# ESP32-Cam-Pico-V2.net
KiCad netlist of a schematic drawn in EAGLE
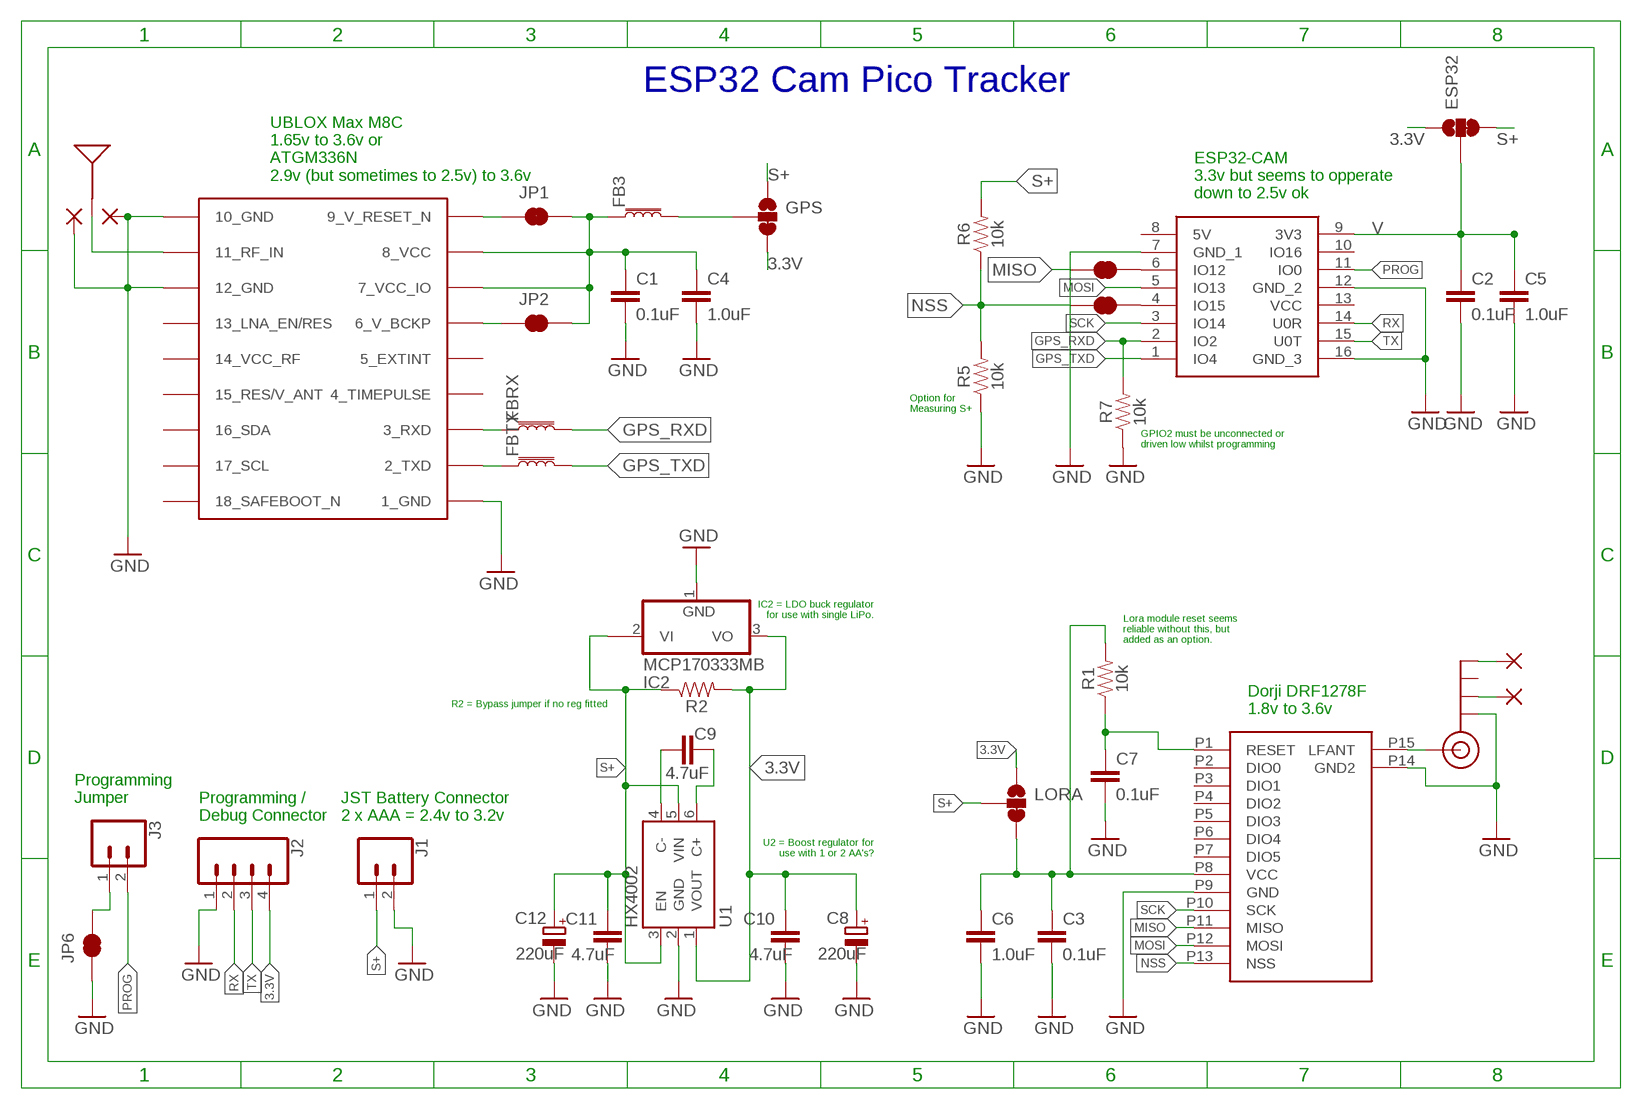
[diagram p0: schematic, sheet 1]

(export (version "E")
  (design (tool "Eeschema 10.0.6"))
  (components
    (comp (ref "C1")
      (value "0.1uF")
      (footprint "eagle-import:0402")
      (libsource (lib "eagle-import") (part "0.1UF-0402-6.3V-10%-X7R"))
    )
    (comp (ref "C2")
      (value "0.1uF")
      (footprint "eagle-import:0402")
      (libsource (lib "eagle-import") (part "0.1UF-0402-6.3V-10%-X7R"))
    )
    (comp (ref "C3")
      (value "0.1uF")
      (footprint "eagle-import:0402")
      (libsource (lib "eagle-import") (part "0.1UF-0402-6.3V-10%-X7R"))
    )
    (comp (ref "C4")
      (value "1.0uF")
      (footprint "eagle-import:0402")
      (libsource (lib "eagle-import") (part "1.0UF-0402-16V-10%"))
    )
    (comp (ref "C5")
      (value "1.0uF")
      (footprint "eagle-import:0402")
      (libsource (lib "eagle-import") (part "1.0UF-0402-16V-10%"))
    )
    (comp (ref "C6")
      (value "1.0uF")
      (footprint "eagle-import:0402")
      (libsource (lib "eagle-import") (part "1.0UF-0402-16V-10%"))
    )
    (comp (ref "C7")
      (value "0.1uF")
      (footprint "eagle-import:0402")
      (libsource (lib "eagle-import") (part "0.1UF-0402-6.3V-10%-X7R"))
    )
    (comp (ref "C8")
      (value "220uF")
      (footprint "eagle-import:SMC_C")
      (libsource (lib "eagle-import") (part "CPOL-EUSMCC"))
    )
    (comp (ref "C9")
      (value "4.7uF")
      (footprint "eagle-import:0402")
      (libsource (lib "eagle-import") (part "1.0UF-0402-16V-10%"))
    )
    (comp (ref "C10")
      (value "4.7uF")
      (footprint "eagle-import:0402")
      (libsource (lib "eagle-import") (part "1.0UF-0402-16V-10%"))
    )
    (comp (ref "C11")
      (value "4.7uF")
      (footprint "eagle-import:0402")
      (libsource (lib "eagle-import") (part "1.0UF-0402-16V-10%"))
    )
    (comp (ref "C12")
      (value "220uF")
      (footprint "eagle-import:SMC_C")
      (libsource (lib "eagle-import") (part "CPOL-EUSMCC"))
    )
    (comp (ref "ESP32")
      (value "JUMPER-SMT_3_1-NC_TRACE_SILK")
      (footprint "eagle-import:SMT-JUMPER_3_1-NC_TRACE_SILK")
      (libsource (lib "eagle-import") (part "JUMPER-SMT_3_1-NC_TRACE_SILK"))
    )
    (comp (ref "FB3")
      (value "FERRITE_BEAD-120_OHM-0402")
      (footprint "eagle-import:0402")
      (fields (field (name "MFG_PART") "BLM15HB121SN1D"))
      (libsource (lib "eagle-import") (part "FERRITE_BEAD-120_OHM-0402"))
    )
    (comp (ref "FBRX")
      (value "FERRITE_BEAD-120_OHM-0402")
      (footprint "eagle-import:0402")
      (fields (field (name "MFG_PART") "BLM15HB121SN1D"))
      (libsource (lib "eagle-import") (part "FERRITE_BEAD-120_OHM-0402"))
    )
    (comp (ref "FBTX")
      (value "FERRITE_BEAD-120_OHM-0402")
      (footprint "eagle-import:0402")
      (fields (field (name "MFG_PART") "BLM15HB121SN1D"))
      (libsource (lib "eagle-import") (part "FERRITE_BEAD-120_OHM-0402"))
    )
    (comp (ref "GPS")
      (value "JUMPER-SMT_3_1-NC_TRACE_SILK")
      (footprint "eagle-import:SMT-JUMPER_3_1-NC_TRACE_SILK")
      (libsource (lib "eagle-import") (part "JUMPER-SMT_3_1-NC_TRACE_SILK"))
    )
    (comp (ref "IC1")
      (value "ESP32-CAM")
      (footprint "eagle-import:ESP32CAM")
      (libsource (lib "eagle-import") (part "ESP32-CAM"))
    )
    (comp (ref "IC2")
      (value "MCP170333MB")
      (footprint "eagle-import:SOT89")
      (libsource (lib "eagle-import") (part "MCP1703MB33"))
    )
    (comp (ref "J$1")
      (value "SMA_EDGE")
      (footprint "eagle-import:SMA-EDGE")
      (libsource (lib "eagle-import") (part "SMA_EDGE"))
    )
    (comp (ref "J1")
      (value "CONN_02JST-PTH-2-KIT")
      (footprint "eagle-import:JST-2-PTH-KIT")
      (libsource (lib "eagle-import") (part "CONN_02JST-PTH-2-KIT"))
    )
    (comp (ref "J2")
      (value "CONN_04LOCK")
      (footprint "eagle-import:1X04_LOCK")
      (libsource (lib "eagle-import") (part "CONN_04LOCK"))
    )
    (comp (ref "J3")
      (value "CONN_02LOCK")
      (footprint "eagle-import:1X02_LOCK")
      (libsource (lib "eagle-import") (part "CONN_02LOCK"))
    )
    (comp (ref "JP1")
      (value "JUMPER-SMT_2_NC_TRACE_NO-SILK")
      (footprint "eagle-import:SMT-JUMPER_2_NC_TRACE_NO-SILK")
      (libsource (lib "eagle-import") (part "JUMPER-SMT_2_NC_TRACE_NO-SILK"))
    )
    (comp (ref "JP2")
      (value "JUMPER-SMT_2_NC_TRACE_NO-SILK")
      (footprint "eagle-import:SMT-JUMPER_2_NC_TRACE_NO-SILK")
      (libsource (lib "eagle-import") (part "JUMPER-SMT_2_NC_TRACE_NO-SILK"))
    )
    (comp (ref "JP6")
      (value "JUMPER-SMT_2_NC_TRACE_NO-SILK")
      (footprint "eagle-import:SMT-JUMPER_2_NC_TRACE_NO-SILK")
      (libsource (lib "eagle-import") (part "JUMPER-SMT_2_NC_TRACE_NO-SILK"))
    )
    (comp (ref "JP9")
      (value "JUMPER-SMT_2_NC_TRACE_NO-SILK")
      (footprint "eagle-import:SMT-JUMPER_2_NC_TRACE_NO-SILK")
      (libsource (lib "eagle-import") (part "JUMPER-SMT_2_NC_TRACE_NO-SILK"))
    )
    (comp (ref "JP10")
      (value "JUMPER-SMT_2_NC_TRACE_NO-SILK")
      (footprint "eagle-import:SMT-JUMPER_2_NC_TRACE_NO-SILK")
      (libsource (lib "eagle-import") (part "JUMPER-SMT_2_NC_TRACE_NO-SILK"))
    )
    (comp (ref "LORA")
      (value "JUMPER-SMT_3_1-NC_TRACE_SILK")
      (footprint "eagle-import:SMT-JUMPER_3_1-NC_TRACE_SILK")
      (libsource (lib "eagle-import") (part "JUMPER-SMT_3_1-NC_TRACE_SILK"))
    )
    (comp (ref "PAD1")
      (value "1,6/0,8")
      (footprint "eagle-import:1,6_0,8")
      (libsource (lib "eagle-import") (part "1,6/0,8"))
    )
    (comp (ref "PAD2")
      (value "1,6/0,8")
      (footprint "eagle-import:1,6_0,8")
      (libsource (lib "eagle-import") (part "1,6/0,8"))
    )
    (comp (ref "PAD3")
      (value "1,6/0,8")
      (footprint "eagle-import:1,6_0,8")
      (libsource (lib "eagle-import") (part "1,6/0,8"))
    )
    (comp (ref "PAD4")
      (value "1,6/0,8")
      (footprint "eagle-import:1,6_0,8")
      (libsource (lib "eagle-import") (part "1,6/0,8"))
    )
    (comp (ref "R1")
      (value "10k")
      (footprint "eagle-import:0402")
      (libsource (lib "eagle-import") (part "10KOHM-0402-1/16W-1%"))
    )
    (comp (ref "R2")
      (value "0k")
      (footprint "eagle-import:0402")
      (libsource (lib "eagle-import") (part "10KOHM-0402-1/16W-1%"))
    )
    (comp (ref "R5")
      (value "10k")
      (footprint "eagle-import:0402")
      (libsource (lib "eagle-import") (part "10KOHM-0402-1/16W-1%"))
    )
    (comp (ref "R6")
      (value "10k")
      (footprint "eagle-import:0402")
      (libsource (lib "eagle-import") (part "10KOHM-0402-1/16W-1%"))
    )
    (comp (ref "R7")
      (value "10k")
      (footprint "eagle-import:0402")
      (libsource (lib "eagle-import") (part "10KOHM-0402-1/16W-1%"))
    )
    (comp (ref "U$1")
      (value "MAX-M8")
      (footprint "eagle-import:MAX-M8")
      (libsource (lib "eagle-import") (part "MAX-M8"))
    )
    (comp (ref "U$2")
      (value "1.575GHz")
      (footprint "eagle-import:ANT-GPS-2X7MM")
      (libsource (lib "eagle-import") (part "ANTENNAGPS-2X7MM"))
    )
    (comp (ref "U$3")
      (value "DRF1278F_2LESS_PINS")
      (footprint "eagle-import:DRF1278F_2_LESS_PINS")
      (libsource (lib "eagle-import") (part "DRF1278F_2LESS_PINS"))
    )
    (comp (ref "U1")
      (value "HX4002")
      (footprint "eagle-import:SOT23-6")
      (libsource (lib "eagle-import") (part "CE021SOT-23"))
    )
  )
  (nets
    (net (code "1") (name "/V") (class "Default")
      (node (ref "C2") (pin "1") (pinfunction "1_1") (pintype "passive"))
      (node (ref "C5") (pin "1") (pinfunction "1_1") (pintype "passive"))
      (node (ref "ESP32") (pin "2") (pinfunction "2_2") (pintype "passive"))
      (node (ref "IC1") (pin "9") (pinfunction "3V3_9") (pintype "bidirectional"))
    )
    (net (code "2") (name "3.3V") (class "Default")
      (node (ref "C10") (pin "1") (pinfunction "1_1") (pintype "passive"))
      (node (ref "C8") (pin "+") (pinfunction "+_+") (pintype "passive"))
      (node (ref "ESP32") (pin "1") (pinfunction "1_1") (pintype "passive"))
      (node (ref "GPS") (pin "3") (pinfunction "3_3") (pintype "passive"))
      (node (ref "IC2") (pin "3") (pinfunction "VO_3") (pintype "passive"))
      (node (ref "J2") (pin "4") (pinfunction "4_4") (pintype "passive"))
      (node (ref "LORA") (pin "1") (pinfunction "1_1") (pintype "passive"))
      (node (ref "R2") (pin "2") (pinfunction "2_2") (pintype "passive"))
      (node (ref "U1") (pin "1") (pinfunction "VOUT_1") (pintype "bidirectional"))
    )
    (net (code "3") (name "GND") (class "Default")
      (node (ref "C1") (pin "2") (pinfunction "2_2") (pintype "passive"))
      (node (ref "C10") (pin "2") (pinfunction "2_2") (pintype "passive"))
      (node (ref "C11") (pin "2") (pinfunction "2_2") (pintype "passive"))
      (node (ref "C12") (pin "-") (pinfunction "-_-") (pintype "passive"))
      (node (ref "C2") (pin "2") (pinfunction "2_2") (pintype "passive"))
      (node (ref "C3") (pin "2") (pinfunction "2_2") (pintype "passive"))
      (node (ref "C4") (pin "2") (pinfunction "2_2") (pintype "passive"))
      (node (ref "C5") (pin "2") (pinfunction "2_2") (pintype "passive"))
      (node (ref "C6") (pin "2") (pinfunction "2_2") (pintype "passive"))
      (node (ref "C7") (pin "2") (pinfunction "2_2") (pintype "passive"))
      (node (ref "C8") (pin "-") (pinfunction "-_-") (pintype "passive"))
      (node (ref "IC1") (pin "12") (pinfunction "GND_2_12") (pintype "bidirectional"))
      (node (ref "IC1") (pin "16") (pinfunction "GND_3_16") (pintype "bidirectional"))
      (node (ref "IC1") (pin "7") (pinfunction "GND_1_7") (pintype "bidirectional"))
      (node (ref "IC2") (pin "1") (pinfunction "GND_1") (pintype "passive"))
      (node (ref "J$1") (pin "GND@0") (pinfunction "GND_GND@0") (pintype "bidirectional"))
      (node (ref "J1") (pin "2") (pinfunction "2_2") (pintype "passive"))
      (node (ref "J2") (pin "1") (pinfunction "1_1") (pintype "passive"))
      (node (ref "JP6") (pin "1") (pinfunction "1_1") (pintype "passive"))
      (node (ref "PAD1") (pin "1") (pinfunction "P_1") (pintype "passive"))
      (node (ref "PAD2") (pin "1") (pinfunction "P_1") (pintype "passive"))
      (node (ref "R5") (pin "1") (pinfunction "1_1") (pintype "passive"))
      (node (ref "R7") (pin "1") (pinfunction "1_1") (pintype "passive"))
      (node (ref "U$1") (pin "10_GND") (pinfunction "10_GND_10_GND") (pintype "power_in"))
      (node (ref "U$1") (pin "12_GND") (pinfunction "12_GND_12_GND") (pintype "power_in"))
      (node (ref "U$1") (pin "1_GND") (pinfunction "1_GND_1_GND") (pintype "power_in"))
      (node (ref "U$3") (pin "P14") (pinfunction "GND2_P14") (pintype "bidirectional"))
      (node (ref "U$3") (pin "P9") (pinfunction "GND_P9") (pintype "bidirectional"))
      (node (ref "U1") (pin "2") (pinfunction "GND_2") (pintype "bidirectional"))
    )
    (net (code "4") (name "GPS_RXD") (class "Default")
      (node (ref "FBRX") (pin "2") (pinfunction "2_2") (pintype "passive"))
      (node (ref "IC1") (pin "2") (pinfunction "IO2_2") (pintype "bidirectional"))
      (node (ref "R7") (pin "2") (pinfunction "2_2") (pintype "passive"))
    )
    (net (code "5") (name "GPS_TXD") (class "Default")
      (node (ref "FBTX") (pin "2") (pinfunction "2_2") (pintype "passive"))
      (node (ref "IC1") (pin "1") (pinfunction "IO4_1") (pintype "bidirectional"))
    )
    (net (code "6") (name "MISO") (class "Default")
      (node (ref "JP9") (pin "1") (pinfunction "1_1") (pintype "passive"))
      (node (ref "U$3") (pin "P11") (pinfunction "MISO_P11") (pintype "bidirectional"))
    )
    (net (code "7") (name "MOSI") (class "Default")
      (node (ref "IC1") (pin "5") (pinfunction "IO13_5") (pintype "bidirectional"))
      (node (ref "U$3") (pin "P12") (pinfunction "MOSI_P12") (pintype "bidirectional"))
    )
    (net (code "8") (name "NSS") (class "Default")
      (node (ref "JP10") (pin "1") (pinfunction "1_1") (pintype "passive"))
      (node (ref "R5") (pin "2") (pinfunction "2_2") (pintype "passive"))
      (node (ref "R6") (pin "1") (pinfunction "1_1") (pintype "passive"))
      (node (ref "U$3") (pin "P13") (pinfunction "NSS_P13") (pintype "bidirectional"))
    )
    (net (code "9") (name "Net-(C1-Pad1)") (class "Default")
      (node (ref "C1") (pin "1") (pinfunction "1_1") (pintype "passive"))
      (node (ref "C4") (pin "1") (pinfunction "1_1") (pintype "passive"))
      (node (ref "FB3") (pin "1") (pinfunction "1_1") (pintype "passive"))
      (node (ref "JP1") (pin "2") (pinfunction "2_2") (pintype "passive"))
      (node (ref "JP2") (pin "2") (pinfunction "2_2") (pintype "passive"))
      (node (ref "U$1") (pin "7_VCC_IO") (pinfunction "7_VCC_IO_7_VCC_IO") (pintype "power_in"))
      (node (ref "U$1") (pin "8_VCC") (pinfunction "8_VCC_8_VCC") (pintype "power_in"))
    )
    (net (code "10") (name "Net-(FB3-Pad2)") (class "Default")
      (node (ref "FB3") (pin "2") (pinfunction "2_2") (pintype "passive"))
      (node (ref "GPS") (pin "2") (pinfunction "2_2") (pintype "passive"))
    )
    (net (code "11") (name "Net-(FBRX-Pad1)") (class "Default")
      (node (ref "FBRX") (pin "1") (pinfunction "1_1") (pintype "passive"))
      (node (ref "U$1") (pin "3_RXD") (pinfunction "3_RXD_3_RXD") (pintype "bidirectional"))
    )
    (net (code "12") (name "Net-(FBTX-Pad1)") (class "Default")
      (node (ref "FBTX") (pin "1") (pinfunction "1_1") (pintype "passive"))
      (node (ref "U$1") (pin "2_TXD") (pinfunction "2_TXD_2_TXD") (pintype "bidirectional"))
    )
    (net (code "13") (name "Net-(IC1-IO12)") (class "Default")
      (node (ref "IC1") (pin "6") (pinfunction "IO12_6") (pintype "bidirectional"))
      (node (ref "JP9") (pin "2") (pinfunction "2_2") (pintype "passive"))
    )
    (net (code "14") (name "Net-(IC1-IO15)") (class "Default")
      (node (ref "IC1") (pin "4") (pinfunction "IO15_4") (pintype "bidirectional"))
      (node (ref "JP10") (pin "2") (pinfunction "2_2") (pintype "passive"))
    )
    (net (code "15") (name "Net-(J$1-SIGNAL)") (class "Default")
      (node (ref "J$1") (pin "SIG") (pinfunction "SIGNAL_SIG") (pintype "bidirectional"))
      (node (ref "U$3") (pin "P15") (pinfunction "LFANT_P15") (pintype "bidirectional"))
    )
    (net (code "16") (name "Net-(J3-Pad1)") (class "Default")
      (node (ref "J3") (pin "1") (pinfunction "1_1") (pintype "passive"))
      (node (ref "JP6") (pin "2") (pinfunction "2_2") (pintype "passive"))
    )
    (net (code "17") (name "Net-(JP2-Pad1)") (class "Default")
      (node (ref "JP2") (pin "1") (pinfunction "1_1") (pintype "passive"))
      (node (ref "U$1") (pin "6_V_BCKP") (pinfunction "6_V_BCKP_6_V_BCKP") (pintype "bidirectional"))
    )
    (net (code "18") (name "Net-(PAD3-P)") (class "Default")
      (node (ref "J$1") (pin "GND@3") (pinfunction "GND_GND@3") (pintype "bidirectional"))
      (node (ref "PAD3") (pin "1") (pinfunction "P_1") (pintype "passive"))
    )
    (net (code "19") (name "Net-(PAD4-P)") (class "Default")
      (node (ref "J$1") (pin "GND@1") (pinfunction "GND_GND@1") (pintype "bidirectional"))
      (node (ref "PAD4") (pin "1") (pinfunction "P_1") (pintype "passive"))
    )
    (net (code "20") (name "Net-(U$1-9_V_RESET_N)") (class "Default")
      (node (ref "JP1") (pin "1") (pinfunction "1_1") (pintype "passive"))
      (node (ref "U$1") (pin "9_RESET_N") (pinfunction "9_V_RESET_N_9_RESET_N") (pintype "power_in"))
    )
    (net (code "21") (name "Net-(U$2-SIGNAL)") (class "Default")
      (node (ref "U$1") (pin "11_RF_IN") (pinfunction "11_RF_IN_11_RF_IN") (pintype "bidirectional"))
      (node (ref "U$2") (pin "1") (pinfunction "SIGNAL_1") (pintype "bidirectional"))
    )
    (net (code "22") (name "Net-(U$3-RESET)") (class "Default")
      (node (ref "C7") (pin "1") (pinfunction "1_1") (pintype "passive"))
      (node (ref "R1") (pin "1") (pinfunction "1_1") (pintype "passive"))
      (node (ref "U$3") (pin "P1") (pinfunction "RESET_P1") (pintype "bidirectional"))
    )
    (net (code "23") (name "Net-(U1-C+)") (class "Default")
      (node (ref "C9") (pin "1") (pinfunction "1_1") (pintype "passive"))
      (node (ref "U1") (pin "6") (pinfunction "C+_6") (pintype "bidirectional"))
    )
    (net (code "24") (name "Net-(U1-C-)") (class "Default")
      (node (ref "C9") (pin "2") (pinfunction "2_2") (pintype "passive"))
      (node (ref "U1") (pin "4") (pinfunction "C-_4") (pintype "bidirectional"))
    )
    (net (code "25") (name "PROG") (class "Default")
      (node (ref "IC1") (pin "11") (pinfunction "IO0_11") (pintype "bidirectional"))
      (node (ref "J3") (pin "2") (pinfunction "2_2") (pintype "passive"))
    )
    (net (code "26") (name "RX") (class "Default")
      (node (ref "IC1") (pin "14") (pinfunction "U0R_14") (pintype "bidirectional"))
      (node (ref "J2") (pin "2") (pinfunction "2_2") (pintype "passive"))
    )
    (net (code "27") (name "S+") (class "Default")
      (node (ref "C11") (pin "1") (pinfunction "1_1") (pintype "passive"))
      (node (ref "C12") (pin "+") (pinfunction "+_+") (pintype "passive"))
      (node (ref "C3") (pin "1") (pinfunction "1_1") (pintype "passive"))
      (node (ref "C6") (pin "1") (pinfunction "1_1") (pintype "passive"))
      (node (ref "ESP32") (pin "3") (pinfunction "3_3") (pintype "passive"))
      (node (ref "GPS") (pin "1") (pinfunction "1_1") (pintype "passive"))
      (node (ref "IC2") (pin "2@1") (pinfunction "VI1_2@1") (pintype "input"))
      (node (ref "J1") (pin "1") (pinfunction "1_1") (pintype "passive"))
      (node (ref "LORA") (pin "2") (pinfunction "2_2") (pintype "passive"))
      (node (ref "LORA") (pin "3") (pinfunction "3_3") (pintype "passive"))
      (node (ref "R1") (pin "2") (pinfunction "2_2") (pintype "passive"))
      (node (ref "R2") (pin "1") (pinfunction "1_1") (pintype "passive"))
      (node (ref "R6") (pin "2") (pinfunction "2_2") (pintype "passive"))
      (node (ref "U$3") (pin "P8") (pinfunction "VCC_P8") (pintype "bidirectional"))
      (node (ref "U1") (pin "3") (pinfunction "EN_3") (pintype "bidirectional"))
      (node (ref "U1") (pin "5") (pinfunction "VIN_5") (pintype "bidirectional"))
    )
    (net (code "28") (name "SCK") (class "Default")
      (node (ref "IC1") (pin "3") (pinfunction "IO14_3") (pintype "bidirectional"))
      (node (ref "U$3") (pin "P10") (pinfunction "SCK_P10") (pintype "bidirectional"))
    )
    (net (code "29") (name "TX") (class "Default")
      (node (ref "IC1") (pin "15") (pinfunction "U0T_15") (pintype "bidirectional"))
      (node (ref "J2") (pin "3") (pinfunction "3_3") (pintype "passive"))
    )
    (net (code "30") (name "unconnected-(IC1-5V-Pad8)") (class "Default")
      (node (ref "IC1") (pin "8") (pinfunction "5V_8") (pintype "bidirectional"))
    )
    (net (code "31") (name "unconnected-(IC1-IO16-Pad10)") (class "Default")
      (node (ref "IC1") (pin "10") (pinfunction "IO16_10") (pintype "bidirectional"))
    )
    (net (code "32") (name "unconnected-(IC1-VCC-Pad13)") (class "Default")
      (node (ref "IC1") (pin "13") (pinfunction "VCC_13") (pintype "bidirectional"))
    )
    (net (code "33") (name "unconnected-(IC2-VI-Pad2)") (class "Default")
      (node (ref "IC2") (pin "2") (pinfunction "VI_2") (pintype "input"))
    )
    (net (code "34") (name "unconnected-(J$1-GND-PadGND@2)") (class "Default")
      (node (ref "J$1") (pin "GND@2") (pinfunction "GND_GND@2") (pintype "bidirectional"))
    )
    (net (code "35") (name "unconnected-(U$1-13_LNA_EN{slash}RES-Pad13_LNA_EN)") (class "Default")
      (node (ref "U$1") (pin "13_LNA_EN") (pinfunction "13_LNA_EN/RES_13_LNA_EN") (pintype "bidirectional"))
    )
    (net (code "36") (name "unconnected-(U$1-15_RES{slash}V_ANT-Pad15_V_ANT{slash}RESERVED)") (class "Default")
      (node (ref "U$1") (pin "15_V_ANT/RESERVED") (pinfunction "15_RES/V_ANT_15_V_ANT/RESERVED") (pintype "bidirectional"))
    )
    (net (code "37") (name "unconnected-(U$1-Pad4_TIMEPULSE)") (class "Default")
      (node (ref "U$1") (pin "4_TIMEPULSE") (pinfunction "4_TIMEPULSE_4_TIMEPULSE") (pintype "bidirectional"))
    )
    (net (code "38") (name "unconnected-(U$1-Pad5_EXTINT)") (class "Default")
      (node (ref "U$1") (pin "5_EXTINT") (pinfunction "5_EXTINT_5_EXTINT") (pintype "bidirectional"))
    )
    (net (code "39") (name "unconnected-(U$1-Pad14_VCC_RF)") (class "Default")
      (node (ref "U$1") (pin "14_VCC_RF") (pinfunction "14_VCC_RF_14_VCC_RF") (pintype "bidirectional"))
    )
    (net (code "40") (name "unconnected-(U$1-Pad16_SDA)") (class "Default")
      (node (ref "U$1") (pin "16_SDA") (pinfunction "16_SDA_16_SDA") (pintype "bidirectional"))
    )
    (net (code "41") (name "unconnected-(U$1-Pad17_SCL)") (class "Default")
      (node (ref "U$1") (pin "17_SCL") (pinfunction "17_SCL_17_SCL") (pintype "bidirectional"))
    )
    (net (code "42") (name "unconnected-(U$1-Pad18_SAFEBOOT_N)") (class "Default")
      (node (ref "U$1") (pin "18_SAFEBOOT_N") (pinfunction "18_SAFEBOOT_N_18_SAFEBOOT_N") (pintype "bidirectional"))
    )
    (net (code "43") (name "unconnected-(U$3-DIO0-PadP2)") (class "Default")
      (node (ref "U$3") (pin "P2") (pinfunction "DIO0_P2") (pintype "bidirectional"))
    )
    (net (code "44") (name "unconnected-(U$3-DIO1-PadP3)") (class "Default")
      (node (ref "U$3") (pin "P3") (pinfunction "DIO1_P3") (pintype "bidirectional"))
    )
    (net (code "45") (name "unconnected-(U$3-DIO2-PadP4)") (class "Default")
      (node (ref "U$3") (pin "P4") (pinfunction "DIO2_P4") (pintype "bidirectional"))
    )
    (net (code "46") (name "unconnected-(U$3-DIO3-PadP5)") (class "Default")
      (node (ref "U$3") (pin "P5") (pinfunction "DIO3_P5") (pintype "bidirectional"))
    )
    (net (code "47") (name "unconnected-(U$3-DIO4-PadP6)") (class "Default")
      (node (ref "U$3") (pin "P6") (pinfunction "DIO4_P6") (pintype "bidirectional"))
    )
    (net (code "48") (name "unconnected-(U$3-DIO5-PadP7)") (class "Default")
      (node (ref "U$3") (pin "P7") (pinfunction "DIO5_P7") (pintype "bidirectional"))
    )
  )
)
